# MMA8452QT_I2C.net
KiCad netlist of a schematic drawn in Altium Designer
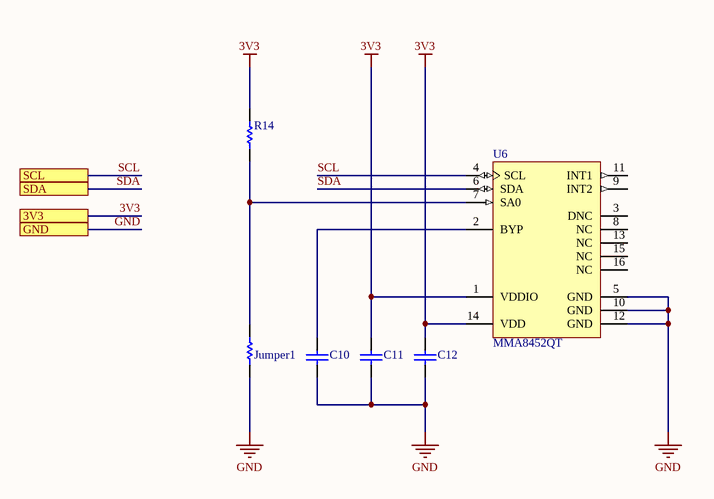
[diagram p0: MMA8452QT_I2C.SchDoc]

(export (version "E")
  (design (tool "Eeschema 10.0.6"))
  (components
    (comp (ref "C10")
      (value "C0805C104J5RAC7800")
      (footprint "CAPC2013X145X50NL20T25")
      (description "0.1µF ±5% 50V Ceramic Capacitor X7R 0805 (2012 Metric)")
      (fields (field (name "MANUFACTURER") "Kemet"))
      (libsource (lib "Altium Content Vault") (part "CAP"))
    )
    (comp (ref "C11")
      (value "C0805C104J5RAC7800")
      (footprint "CAPC2013X145X50NL20T25")
      (description "0.1µF ±5% 50V Ceramic Capacitor X7R 0805 (2012 Metric)")
      (fields (field (name "MANUFACTURER") "Kemet"))
      (libsource (lib "Altium Content Vault") (part "CAP"))
    )
    (comp (ref "C12")
      (value "08053D475KAT2A")
      (footprint "CAPC2013X140X50NL20T25")
      (description "4.7µF ±10% 25V Ceramic Capacitor X5R 0805 (2012 Metric)")
      (fields (field (name "MANUFACTURER") "AVX Interconnect / Elco"))
      (libsource (lib "Altium Content Vault") (part "CAP"))
    )
    (comp (ref "Jumper1")
      (value "~")
      (footprint "RESC2013X60X40NL20T25_A")
      (fields (field (name "TOLERANCE") "0.1%") (field (name "MANUFACTURER") "Panasonic"))
      (libsource (lib "Altium Content Vault") (part "RES-2"))
    )
    (comp (ref "R14")
      (value "RK73B2ATTD103J")
      (footprint "RESC2013X60X30NL20T20")
      (fields (field (name "MANUFACTURER") "KOA Speer"))
      (libsource (lib "Altium Content Vault") (part "RES"))
    )
    (comp (ref "U6")
      (value "MMA8452QT")
      (footprint "FRES-SOT1676-1_V")
      (fields (field (name "MANUFACTURER") "Freescale"))
      (libsource (lib "Altium Content Vault") (part "FRES-MMA8452Q-QFN-16"))
    )
  )
  (nets
    (net (code "1") (name "/SCL") (class "Default")
      (node (ref "U6") (pin "4") (pinfunction "SCL_4") (pintype "bidirectional"))
    )
    (net (code "2") (name "/SDA") (class "Default")
      (node (ref "U6") (pin "6") (pinfunction "SDA_6") (pintype "bidirectional"))
    )
    (net (code "3") (name "3V3") (class "Default")
      (node (ref "C11") (pin "2") (pinfunction "2_2") (pintype "passive"))
      (node (ref "C12") (pin "2") (pinfunction "2_2") (pintype "passive"))
      (node (ref "R14") (pin "2") (pinfunction "2_2") (pintype "passive"))
      (node (ref "U6") (pin "1") (pinfunction "VDDIO_1") (pintype "power_in"))
      (node (ref "U6") (pin "14") (pinfunction "VDD_14") (pintype "power_in"))
    )
    (net (code "4") (name "GND") (class "Default")
      (node (ref "C10") (pin "1") (pinfunction "1_1") (pintype "passive"))
      (node (ref "C11") (pin "1") (pinfunction "1_1") (pintype "passive"))
      (node (ref "C12") (pin "1") (pinfunction "1_1") (pintype "passive"))
      (node (ref "Jumper1") (pin "1") (pinfunction "1_1") (pintype "passive"))
      (node (ref "U6") (pin "10") (pinfunction "GND_10") (pintype "power_in"))
      (node (ref "U6") (pin "12") (pinfunction "GND_12") (pintype "power_in"))
      (node (ref "U6") (pin "5") (pinfunction "GND_5") (pintype "power_in"))
    )
    (net (code "5") (name "Net-(U6-BYP)") (class "Default")
      (node (ref "C10") (pin "2") (pinfunction "2_2") (pintype "passive"))
      (node (ref "U6") (pin "2") (pinfunction "BYP_2") (pintype "passive"))
    )
    (net (code "6") (name "Net-(U6-SA0)") (class "Default")
      (node (ref "Jumper1") (pin "2") (pinfunction "2_2") (pintype "passive"))
      (node (ref "R14") (pin "1") (pinfunction "1_1") (pintype "passive"))
      (node (ref "U6") (pin "7") (pinfunction "SA0_7") (pintype "input"))
    )
    (net (code "7") (name "unconnected-(U6-DNC-Pad3)") (class "Default")
      (node (ref "U6") (pin "3") (pinfunction "DNC_3") (pintype "passive"))
    )
    (net (code "8") (name "unconnected-(U6-INT1-Pad11)") (class "Default")
      (node (ref "U6") (pin "11") (pinfunction "INT1_11") (pintype "output"))
    )
    (net (code "9") (name "unconnected-(U6-INT2-Pad9)") (class "Default")
      (node (ref "U6") (pin "9") (pinfunction "INT2_9") (pintype "output"))
    )
    (net (code "10") (name "unconnected-(U6-NC-Pad8)") (class "Default")
      (node (ref "U6") (pin "8") (pinfunction "NC_8") (pintype "passive"))
    )
    (net (code "11") (name "unconnected-(U6-NC-Pad13)") (class "Default")
      (node (ref "U6") (pin "13") (pinfunction "NC_13") (pintype "passive"))
    )
    (net (code "12") (name "unconnected-(U6-NC-Pad15)") (class "Default")
      (node (ref "U6") (pin "15") (pinfunction "NC_15") (pintype "passive"))
    )
    (net (code "13") (name "unconnected-(U6-NC-Pad16)") (class "Default")
      (node (ref "U6") (pin "16") (pinfunction "NC_16") (pintype "passive"))
    )
  )
)
